# Timer_555.net
KiCad netlist of a schematic drawn in Altium Designer
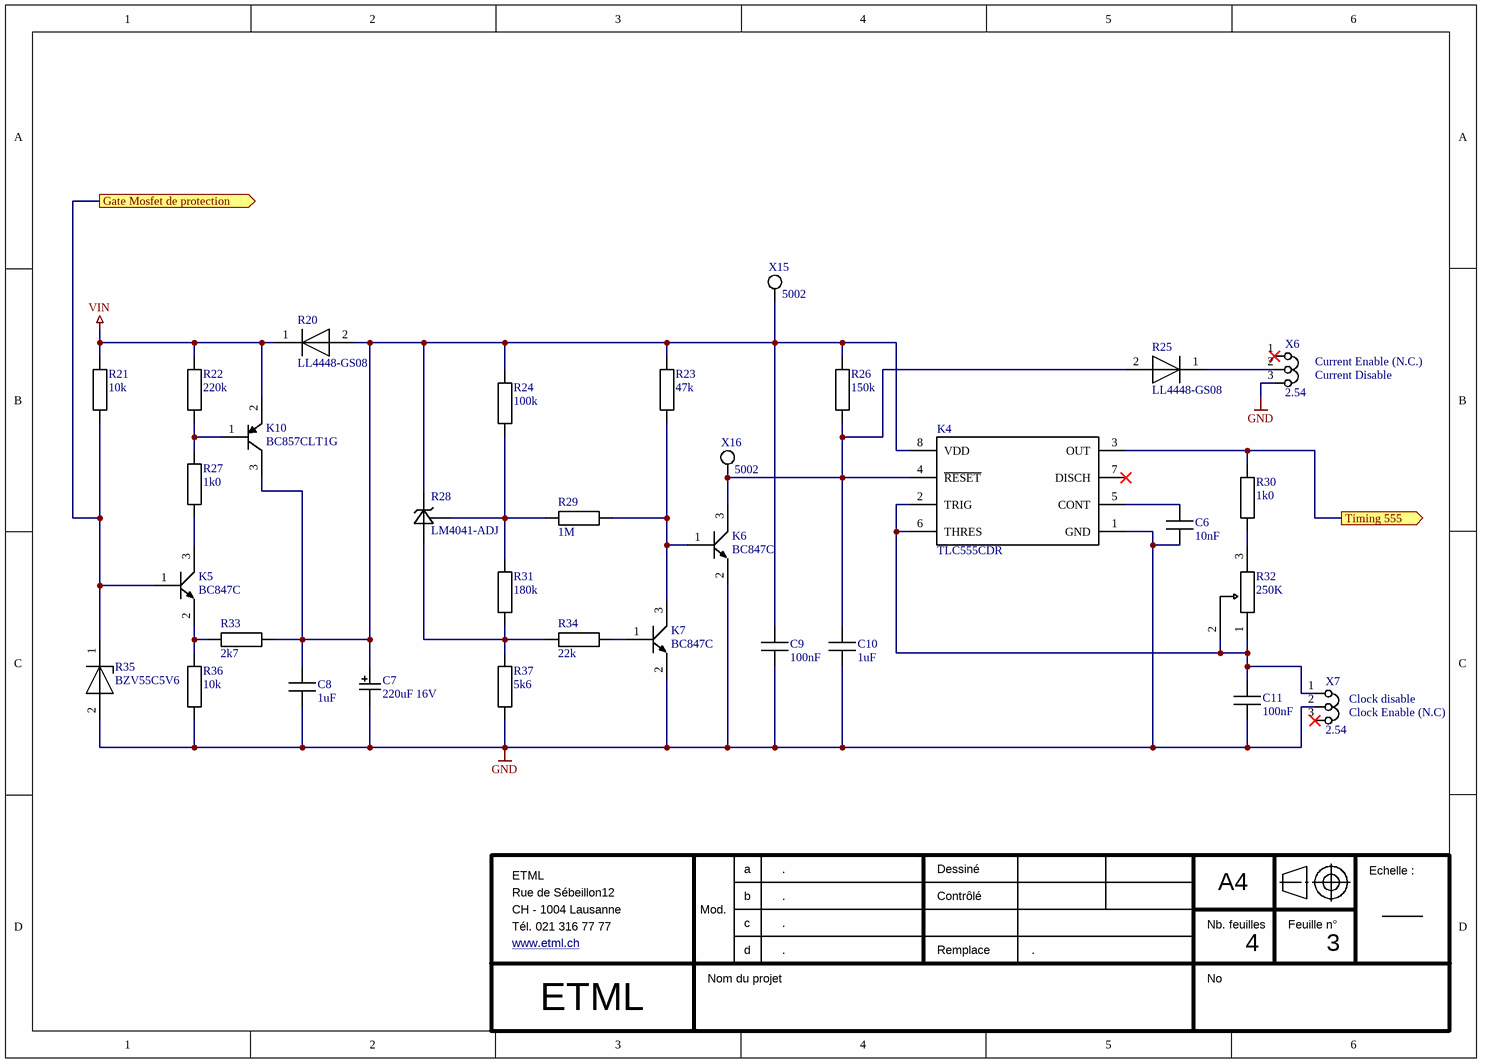
[diagram p0: Timer 555.SchDoc]

(export (version "E")
  (design (tool "Eeschema 10.0.6"))
  (components
    (comp (ref "C6")
      (value "10nF")
      (footprint "CAPC1608X08M")
      (description "CAPC 10nF X7R 50V 10% 1608 (0603 INCH)")
      (fields (field (name "MANUFACTURER") "TDK") (field (name "VOLTAGE") "50V"))
      (libsource (lib "ETML-ES") (part "CAP"))
    )
    (comp (ref "C7")
      (value "220uF 16V")
      (footprint "NIC-CAPA2-6.3X7.7_V")
      (fields (field (name "PARTNUMBER") "UUD1C221MCL1GS") (field (name "MANUFACTURER") "Nichicon"))
      (libsource (lib "Custom components") (part "CMP-0687-00060-1_2"))
    )
    (comp (ref "C8")
      (value "1uF")
      (footprint "CAPC2012X08M")
      (description "CAPC 1uF X5R 25V 10% 2012 (0805 INCH)")
      (fields (field (name "MANUFACTURER") "TDK") (field (name "TOLERANCE") "±10%"))
      (libsource (lib "ETML-ES") (part "CAP"))
    )
    (comp (ref "C9")
      (value "100nF")
      (footprint "CAPC2012X08M")
      (description "CAPC 100nF X7R 50V 10% 2012 (0805 INCH)")
      (fields (field (name "VOLTAGE") "50V") (field (name "MANUFACTURER") "TDK"))
      (libsource (lib "ETML-ES") (part "CAP"))
    )
    (comp (ref "C10")
      (value "1uF")
      (footprint "CAPC2012X08M")
      (description "CAPC 1uF X5R 25V 10% 2012 (0805 INCH)")
      (fields (field (name "MANUFACTURER") "TDK") (field (name "TOLERANCE") "±10%"))
      (libsource (lib "ETML-ES") (part "CAP"))
    )
    (comp (ref "C11")
      (value "100nF")
      (footprint "CAPC2012X08M")
      (description "CAPC 100nF X7R 50V 10% 2012 (0805 INCH)")
      (fields (field (name "VOLTAGE") "50V") (field (name "MANUFACTURER") "TDK"))
      (libsource (lib "ETML-ES") (part "CAP"))
    )
    (comp (ref "K4")
      (value "TLC555CDR")
      (footprint "D0008A_M")
      (description "IC OSC SGL TIMER 2.1MHZ 8-SOIC")
      (libsource (lib "Custom components") (part "CMP-04857-000001-1"))
    )
    (comp (ref "K5")
      (value "BC847C")
      (footprint "SOT90P240X110-3M")
      (description "NPN general purpose transistor")
      (libsource (lib "Custom components") (part "BC847C"))
    )
    (comp (ref "K6")
      (value "BC847C")
      (footprint "SOT90P240X110-3M")
      (description "NPN general purpose transistor")
      (libsource (lib "Custom components") (part "BC847C"))
    )
    (comp (ref "K7")
      (value "BC847C")
      (footprint "SOT90P240X110-3M")
      (description "NPN general purpose transistor")
      (libsource (lib "Custom components") (part "BC847C"))
    )
    (comp (ref "K10")
      (value "BC857CLT1G")
      (footprint "SOT90P240X110-3M")
      (description "General Purpose Transistor, PNP Silicon, 3-Pin SOT-23, Pb-Free, Tape and Reel")
      (fields (field (name "MANUFACTURER") "On Semiconductor"))
      (libsource (lib "Custom components") (part "CMP-1048-00802-1"))
    )
    (comp (ref "R20")
      (value "LL4448-GS08")
      (footprint "FP-6_560-5005_01-4-MFG")
      (description "DIODE GEN PURP 75V 150MA SOD80")
      (fields
        (field (name "MANUFACTURER") "Vishay Small Signal")
        (field (name "OCTOPART") "https://octopart.com/ll4448-gs08-vishay+small+signal-40886")
      )
      (libsource (lib "Custom components") (part "LL4448-GS08"))
    )
    (comp (ref "R21")
      (value "10k")
      (footprint "RESC2012X06M")
      (description "RES 10kohm  ±1% 0.125W 2012 (0805 INCH)")
      (fields (field (name "TOLERANCE") "±1%") (field (name "VOLTAGE") "150V"))
      (libsource (lib "ETML-ES") (part "RES"))
    )
    (comp (ref "R22")
      (value "220k")
      (footprint "RESC2012X06M")
      (description "RES 220kohm  ±1% 0.125W 2012 (0805 INCH)")
      (fields (field (name "POWER") "0.125W") (field (name "TOLERANCE") "±1%"))
      (libsource (lib "ETML-ES") (part "RES"))
    )
    (comp (ref "R23")
      (value "47k")
      (footprint "RESC2012X06M")
      (description "RES 47kohm  ±1% 0.125W 2012 (0805 INCH)")
      (fields (field (name "MANUFACTURER") "Yageo") (field (name "VOLTAGE") "150V"))
      (libsource (lib "ETML-ES") (part "RES"))
    )
    (comp (ref "R24")
      (value "100k")
      (footprint "RESC2012X06M")
      (description "RES 100kohm  ±1% 0.125W 2012 (0805 INCH)")
      (fields (field (name "MANUFACTURER") "Yageo") (field (name "VOLTAGE") "150V"))
      (libsource (lib "ETML-ES") (part "RES"))
    )
    (comp (ref "R25")
      (value "LL4448-GS08")
      (footprint "FP-6_560-5005_01-4-MFG")
      (description "DIODE GEN PURP 75V 150MA SOD80")
      (fields
        (field (name "MANUFACTURER") "Vishay Small Signal")
        (field (name "OCTOPART") "https://octopart.com/ll4448-gs08-vishay+small+signal-40886")
      )
      (libsource (lib "Custom components") (part "LL4448-GS08"))
    )
    (comp (ref "R26")
      (value "150k")
      (footprint "RESC2012X06M")
      (description "RES 150kohm  ±1% 0.125W 2012 (0805 INCH)")
      (fields (field (name "TOLERANCE") "±1%") (field (name "VOLTAGE") "150V"))
      (libsource (lib "ETML-ES") (part "RES"))
    )
    (comp (ref "R27")
      (value "1k0")
      (footprint "RESC2012X06M")
      (description "RES 1.0kohm  ±1% 0.125W 2012 (0805 INCH)")
      (fields (field (name "MANUFACTURER") "Yageo") (field (name "TOLERANCE") "±1%"))
      (libsource (lib "ETML-ES") (part "RES"))
    )
    (comp (ref "R28")
      (value "LM4041-ADJ")
      (footprint "SOT90P240X110-3M")
      (description "Precision Micropower Shunt Voltage Reference, 3-pin SOT-23")
      (fields (field (name "MANUFACTURER") "Texas Instruments"))
      (libsource (lib "Custom components") (part "LM4041"))
    )
    (comp (ref "R29")
      (value "1M")
      (footprint "RESC2012X06M")
      (description "RES 1.0Mohm  ±1% 0.125W 2012 (0805 INCH)")
      (fields (field (name "MANUFACTURER") "Yageo") (field (name "VOLTAGE") "150V"))
      (libsource (lib "ETML-ES") (part "RES"))
    )
    (comp (ref "R30")
      (value "1k0")
      (footprint "RESC2012X06M")
      (description "RES 1.0kohm  ±1% 0.125W 2012 (0805 INCH)")
      (fields (field (name "MANUFACTURER") "Yageo") (field (name "TOLERANCE") "±1%"))
      (libsource (lib "ETML-ES") (part "RES"))
    )
    (comp (ref "R31")
      (value "180k")
      (footprint "RESC2012X06M")
      (description "RES 180kohm  ±1% 0.125W 2012 (0805 INCH)")
      (fields (field (name "MANUFACTURER") "Yageo") (field (name "POWER") "0.125W"))
      (libsource (lib "ETML-ES") (part "RES"))
    )
    (comp (ref "R32")
      (value "250K")
      (footprint "FP-3296W-MFG")
      (description "TRIMMER 250K OHM 0.5W PC PIN TOP")
      (fields
        (field (name "OCTOPART") "https://octopart.com/3296w-1-254lf-bourns-574856")
        (field (name "MANUFACTURER") "Bourns")
      )
      (libsource (lib "Custom components") (part "Trimmer250K"))
    )
    (comp (ref "R33")
      (value "2k7")
      (footprint "RESC2012X06M")
      (description "RES 2.7kohm  ±1% 0.125W 2012 (0805 INCH)")
      (fields (field (name "POWER") "0.125W") (field (name "MANUFACTURER") "Yageo"))
      (libsource (lib "ETML-ES") (part "RES"))
    )
    (comp (ref "R34")
      (value "22k")
      (footprint "RESC2012X06M")
      (description "RES 22kohm  ±1% 0.125W 2012 (0805 INCH)")
      (fields (field (name "TOLERANCE") "±1%") (field (name "MANUFACTURER") "Yageo"))
      (libsource (lib "ETML-ES") (part "RES"))
    )
    (comp (ref "R35")
      (value "BZV55C5V6")
      (footprint "FP-DO-213AA-MFG")
      (description "BZV55C5V6 Diode Zener Single 5.6V 2% 3.33mW 2-Pin MELF DO-213AA Bag")
      (fields (field (name "TOLERANCE") "7%"))
      (libsource (lib "Custom components") (part "CMP-00252-16640727-1"))
    )
    (comp (ref "R36")
      (value "10k")
      (footprint "RESC2012X06M")
      (description "RES 10kohm  ±1% 0.125W 2012 (0805 INCH)")
      (fields (field (name "TOLERANCE") "±1%") (field (name "VOLTAGE") "150V"))
      (libsource (lib "ETML-ES") (part "RES"))
    )
    (comp (ref "R37")
      (value "5k6")
      (footprint "RESC2012X06M")
      (description "RES 5.6kohm  ±1% 0.125W 2012 (0805 INCH)")
      (fields (field (name "POWER") "0.125W") (field (name "MANUFACTURER") "Yageo"))
      (libsource (lib "ETML-ES") (part "RES"))
    )
    (comp (ref "X6")
      (value "2.54")
      (footprint "PIN-1x03-2.54")
      (description "JUMPER 2.54 1x03")
      (fields (field (name "MANUFACTURER") "Würth Electronik") (field (name "VOLTAGE") "250VAC"))
      (libsource (lib "ETML-ES") (part "JUMP-1x3"))
    )
    (comp (ref "X7")
      (value "2.54")
      (footprint "PIN-1x03-2.54")
      (description "JUMPER 2.54 1x03")
      (fields (field (name "MANUFACTURER") "Würth Electronik") (field (name "VOLTAGE") "250VAC"))
      (libsource (lib "ETML-ES") (part "JUMP-1x3"))
    )
    (comp (ref "X15")
      (value "5002")
      (footprint "Keystone_5002")
      (description "TEST THT MINIATURE WT")
      (fields (field (name "MANUFACTURER") "Keystone"))
      (libsource (lib "Custom components") (part "TEST"))
    )
    (comp (ref "X16")
      (value "5002")
      (footprint "Keystone_5002")
      (description "TEST THT MINIATURE WT")
      (fields (field (name "MANUFACTURER") "Keystone"))
      (libsource (lib "Custom components") (part "TEST"))
    )
  )
  (nets
    (net (code "1") (name "/Gate Mosfet de protection") (class "Default")
      (node (ref "K5") (pin "1") (pinfunction "Base_1") (pintype "passive"))
      (node (ref "R21") (pin "1") (pinfunction "1_1") (pintype "passive"))
      (node (ref "R35") (pin "1") (pinfunction "C_1") (pintype "passive"))
    )
    (net (code "2") (name "/Timing 555") (class "Default")
      (node (ref "K4") (pin "3") (pinfunction "OUT_3") (pintype "passive"))
      (node (ref "R30") (pin "2") (pinfunction "2_2") (pintype "passive"))
    )
    (net (code "3") (name "GND") (class "Default")
      (node (ref "C10") (pin "1") (pinfunction "1_1") (pintype "passive"))
      (node (ref "C11") (pin "1") (pinfunction "1_1") (pintype "passive"))
      (node (ref "C6") (pin "1") (pinfunction "1_1") (pintype "passive"))
      (node (ref "C7") (pin "2") (pinfunction "2_2") (pintype "passive"))
      (node (ref "C8") (pin "1") (pinfunction "1_1") (pintype "passive"))
      (node (ref "C9") (pin "1") (pinfunction "1_1") (pintype "passive"))
      (node (ref "K4") (pin "1") (pinfunction "GND_1") (pintype "power_in"))
      (node (ref "K6") (pin "2") (pinfunction "Collector_2") (pintype "passive"))
      (node (ref "K7") (pin "2") (pinfunction "Collector_2") (pintype "passive"))
      (node (ref "R35") (pin "2") (pinfunction "A_2") (pintype "passive"))
      (node (ref "R36") (pin "1") (pinfunction "1_1") (pintype "passive"))
      (node (ref "R37") (pin "1") (pinfunction "1_1") (pintype "passive"))
      (node (ref "X6") (pin "3") (pinfunction "3_3") (pintype "passive"))
      (node (ref "X7") (pin "2") (pinfunction "2_2") (pintype "passive"))
    )
    (net (code "4") (name "Net-(K4-CONT)") (class "Default")
      (node (ref "C6") (pin "2") (pinfunction "2_2") (pintype "passive"))
      (node (ref "K4") (pin "5") (pinfunction "CONT_5") (pintype "power_in"))
    )
    (net (code "5") (name "Net-(K4-THRES)") (class "Default")
      (node (ref "C11") (pin "2") (pinfunction "2_2") (pintype "passive"))
      (node (ref "K4") (pin "2") (pinfunction "TRIG_2") (pintype "power_in"))
      (node (ref "K4") (pin "6") (pinfunction "THRES_6") (pintype "power_in"))
      (node (ref "R32") (pin "1") (pinfunction "CCW_1") (pintype "passive"))
      (node (ref "R32") (pin "2") (pinfunction "WIPER_2") (pintype "passive"))
      (node (ref "X7") (pin "1") (pinfunction "0_1") (pintype "passive"))
    )
    (net (code "6") (name "Net-(K4-~{RESET})") (class "Default")
      (node (ref "C10") (pin "2") (pinfunction "2_2") (pintype "passive"))
      (node (ref "K4") (pin "4") (pinfunction "~{RESET}_4") (pintype "power_in"))
      (node (ref "K6") (pin "3") (pinfunction "Emitter_3") (pintype "passive"))
      (node (ref "R25") (pin "2") (pinfunction "A_2") (pintype "passive"))
      (node (ref "R26") (pin "1") (pinfunction "1_1") (pintype "passive"))
      (node (ref "X16") (pin "1") (pinfunction "TP_1") (pintype "passive"))
    )
    (net (code "7") (name "Net-(K5-Collector)") (class "Default")
      (node (ref "K5") (pin "2") (pinfunction "Collector_2") (pintype "passive"))
      (node (ref "R33") (pin "1") (pinfunction "1_1") (pintype "passive"))
      (node (ref "R36") (pin "2") (pinfunction "2_2") (pintype "passive"))
    )
    (net (code "8") (name "Net-(K5-Emitter)") (class "Default")
      (node (ref "K5") (pin "3") (pinfunction "Emitter_3") (pintype "passive"))
      (node (ref "R27") (pin "1") (pinfunction "1_1") (pintype "passive"))
    )
    (net (code "9") (name "Net-(K6-Base)") (class "Default")
      (node (ref "K6") (pin "1") (pinfunction "Base_1") (pintype "passive"))
      (node (ref "K7") (pin "3") (pinfunction "Emitter_3") (pintype "passive"))
      (node (ref "R23") (pin "1") (pinfunction "1_1") (pintype "passive"))
      (node (ref "R29") (pin "1") (pinfunction "1_1") (pintype "passive"))
    )
    (net (code "10") (name "Net-(K7-Base)") (class "Default")
      (node (ref "K7") (pin "1") (pinfunction "Base_1") (pintype "passive"))
      (node (ref "R34") (pin "2") (pinfunction "2_2") (pintype "passive"))
    )
    (net (code "11") (name "Net-(K10-B)") (class "Default")
      (node (ref "K10") (pin "1") (pinfunction "B_1") (pintype "passive"))
      (node (ref "R22") (pin "1") (pinfunction "1_1") (pintype "passive"))
      (node (ref "R27") (pin "2") (pinfunction "2_2") (pintype "passive"))
    )
    (net (code "12") (name "Net-(K10-C)") (class "Default")
      (node (ref "C7") (pin "1") (pinfunction "1_1") (pintype "passive"))
      (node (ref "C8") (pin "2") (pinfunction "2_2") (pintype "passive"))
      (node (ref "C9") (pin "2") (pinfunction "2_2") (pintype "passive"))
      (node (ref "K10") (pin "3") (pinfunction "C_3") (pintype "passive"))
      (node (ref "K4") (pin "8") (pinfunction "VDD_8") (pintype "power_in"))
      (node (ref "R20") (pin "2") (pinfunction "A_2") (pintype "passive"))
      (node (ref "R23") (pin "2") (pinfunction "2_2") (pintype "passive"))
      (node (ref "R24") (pin "2") (pinfunction "2_2") (pintype "passive"))
      (node (ref "R26") (pin "2") (pinfunction "2_2") (pintype "passive"))
      (node (ref "R28") (pin "2") (pinfunction "+V_2") (pintype "passive"))
      (node (ref "R33") (pin "2") (pinfunction "2_2") (pintype "passive"))
      (node (ref "X15") (pin "1") (pinfunction "TP_1") (pintype "passive"))
    )
    (net (code "13") (name "Net-(R25-C)") (class "Default")
      (node (ref "R25") (pin "1") (pinfunction "C_1") (pintype "passive"))
      (node (ref "X6") (pin "2") (pinfunction "2_2") (pintype "passive"))
    )
    (net (code "14") (name "Net-(R28--V)") (class "Default")
      (node (ref "R28") (pin "3") (pinfunction "-V_3") (pintype "passive"))
      (node (ref "R31") (pin "1") (pinfunction "1_1") (pintype "passive"))
      (node (ref "R34") (pin "1") (pinfunction "1_1") (pintype "passive"))
      (node (ref "R37") (pin "2") (pinfunction "2_2") (pintype "passive"))
    )
    (net (code "15") (name "Net-(R28-FB)") (class "Default")
      (node (ref "R24") (pin "1") (pinfunction "1_1") (pintype "passive"))
      (node (ref "R28") (pin "1") (pinfunction "FB_1") (pintype "power_in"))
      (node (ref "R29") (pin "2") (pinfunction "2_2") (pintype "passive"))
      (node (ref "R31") (pin "2") (pinfunction "2_2") (pintype "passive"))
    )
    (net (code "16") (name "Net-(R32-CW)") (class "Default")
      (node (ref "R30") (pin "1") (pinfunction "1_1") (pintype "passive"))
      (node (ref "R32") (pin "3") (pinfunction "CW_3") (pintype "passive"))
    )
    (net (code "17") (name "VIN") (class "Default")
      (node (ref "K10") (pin "2") (pinfunction "E_2") (pintype "passive"))
      (node (ref "R20") (pin "1") (pinfunction "C_1") (pintype "passive"))
      (node (ref "R21") (pin "2") (pinfunction "2_2") (pintype "passive"))
      (node (ref "R22") (pin "2") (pinfunction "2_2") (pintype "passive"))
    )
    (net (code "18") (name "unconnected-(K4-DISCH-Pad7)") (class "Default")
      (node (ref "K4") (pin "7") (pinfunction "DISCH_7") (pintype "power_in+no_connect"))
    )
    (net (code "19") (name "unconnected-(X6-0-Pad1)") (class "Default")
      (node (ref "X6") (pin "1") (pinfunction "0_1") (pintype "passive+no_connect"))
    )
    (net (code "20") (name "unconnected-(X7-Pad3)") (class "Default")
      (node (ref "X7") (pin "3") (pinfunction "3_3") (pintype "passive+no_connect"))
    )
  )
)
